# 1DDR3L_16bits.net
KiCad netlist of a schematic drawn in Altium Designer
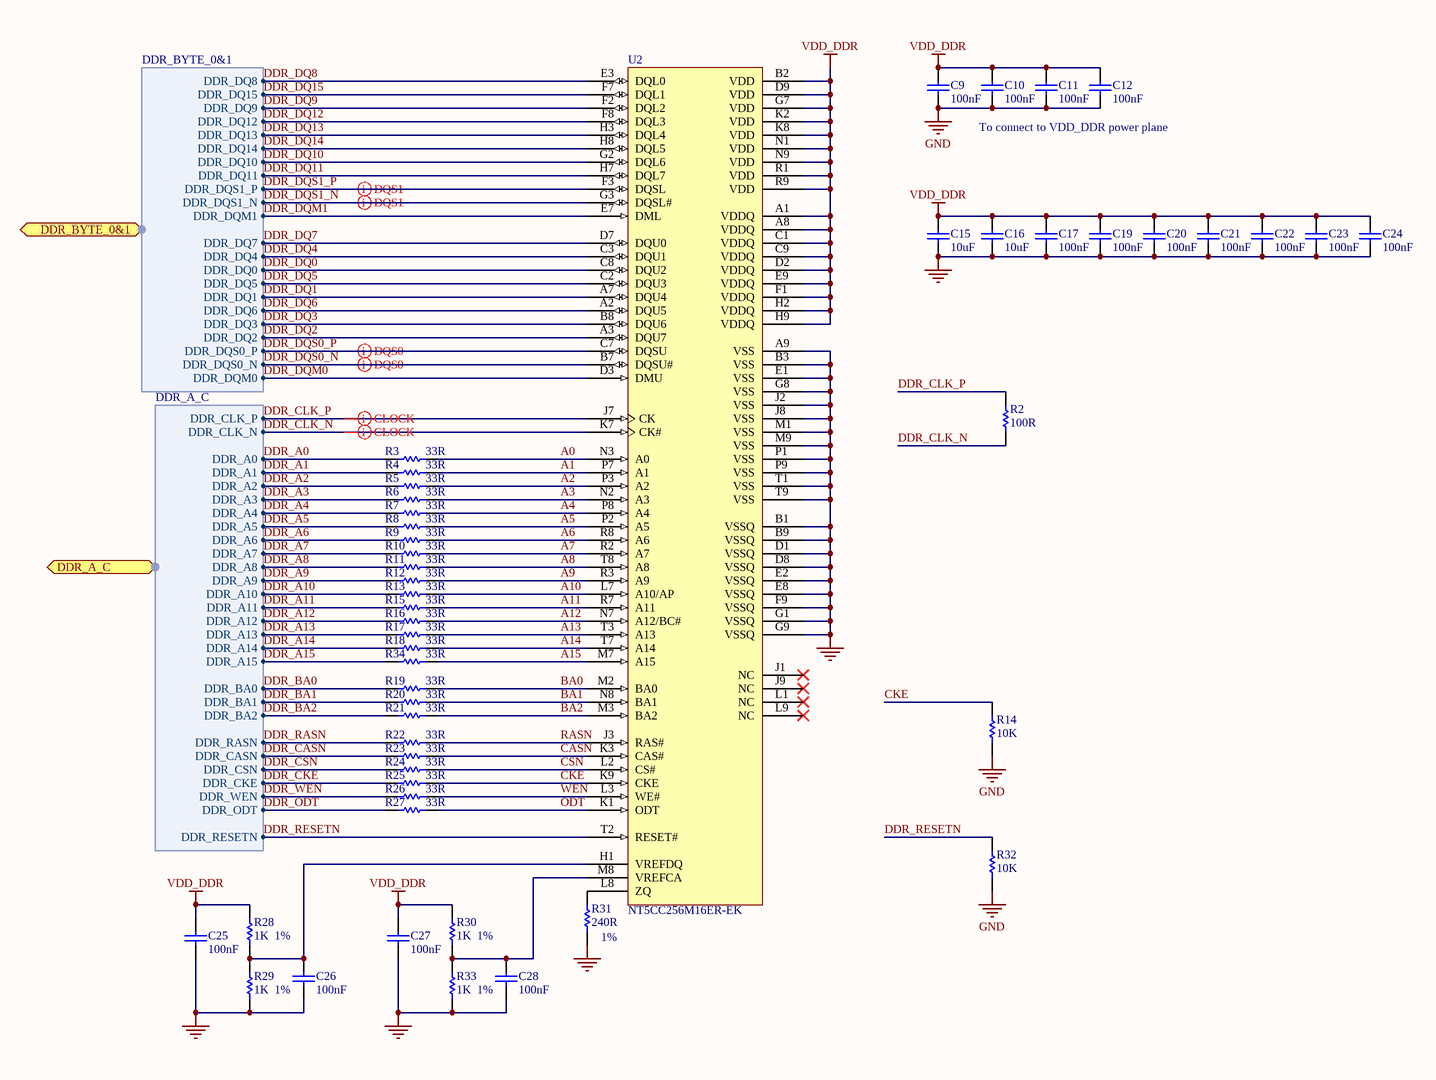
[diagram p0: 1DDR3L_16bits.SchDoc]

(export (version "E")
  (design (tool "Eeschema 10.0.6"))
  (components
    (comp (ref "C9")
      (value "100nF")
      (footprint "C0402")
      (description "Capacitor, MLCC, 100nF, 16V, X7R, 10%, 0402, T=0.5mm")
      (fields
        (field (name "INTERNAL_PART_NUMBER") "MCD-00006")
        (field (name "MANUFACTURER_PART_NUMBER") "CC0402KRX7R7BB104")
        (field (name "PROVIDED_BY") "SUBCO")
      )
      (libsource (lib "MCD_PARTS_database") (part "Capacitor"))
    )
    (comp (ref "C10")
      (value "100nF")
      (footprint "C0402")
      (description "Capacitor, MLCC, 100nF, 16V, X7R, 10%, 0402, T=0.5mm")
      (fields
        (field (name "INTERNAL_PART_NUMBER") "MCD-00006")
        (field (name "MANUFACTURER_PART_NUMBER") "CC0402KRX7R7BB104")
        (field (name "PROVIDED_BY") "SUBCO")
      )
      (libsource (lib "MCD_PARTS_database") (part "Capacitor"))
    )
    (comp (ref "C11")
      (value "100nF")
      (footprint "C0402")
      (description "Capacitor, MLCC, 100nF, 16V, X7R, 10%, 0402, T=0.5mm")
      (fields
        (field (name "INTERNAL_PART_NUMBER") "MCD-00006")
        (field (name "MANUFACTURER_PART_NUMBER") "CC0402KRX7R7BB104")
        (field (name "PROVIDED_BY") "SUBCO")
      )
      (libsource (lib "MCD_PARTS_database") (part "Capacitor"))
    )
    (comp (ref "C12")
      (value "100nF")
      (footprint "C0402")
      (description "Capacitor, MLCC, 100nF, 16V, X7R, 10%, 0402, T=0.5mm")
      (fields
        (field (name "INTERNAL_PART_NUMBER") "MCD-00006")
        (field (name "MANUFACTURER_PART_NUMBER") "CC0402KRX7R7BB104")
        (field (name "PROVIDED_BY") "SUBCO")
      )
      (libsource (lib "MCD_PARTS_database") (part "Capacitor"))
    )
    (comp (ref "C15")
      (value "10uF")
      (footprint "C0603")
      (description "Capacitor, MLCC, 10uF, 10V, X5R, 10%, 0603, T=0,8mm")
      (fields
        (field (name "INTERNAL_PART_NUMBER") "MCD-00099")
        (field (name "MANUFACTURER_PART_NUMBER") "GRM188R61A106KE69D")
        (field (name "PROVIDED_BY") "SUBCO")
      )
      (libsource (lib "MCD_PARTS_database") (part "Capacitor"))
    )
    (comp (ref "C16")
      (value "10uF")
      (footprint "C0603")
      (description "Capacitor, MLCC, 10uF, 10V, X5R, 10%, 0603, T=0,8mm")
      (fields
        (field (name "INTERNAL_PART_NUMBER") "MCD-00099")
        (field (name "MANUFACTURER_PART_NUMBER") "GRM188R61A106KE69D")
        (field (name "PROVIDED_BY") "SUBCO")
      )
      (libsource (lib "MCD_PARTS_database") (part "Capacitor"))
    )
    (comp (ref "C17")
      (value "100nF")
      (footprint "C0402")
      (description "Capacitor, MLCC, 100nF, 16V, X7R, 10%, 0402, T=0.5mm")
      (fields
        (field (name "INTERNAL_PART_NUMBER") "MCD-00006")
        (field (name "MANUFACTURER_PART_NUMBER") "CC0402KRX7R7BB104")
        (field (name "PROVIDED_BY") "SUBCO")
      )
      (libsource (lib "MCD_PARTS_database") (part "Capacitor"))
    )
    (comp (ref "C19")
      (value "100nF")
      (footprint "C0402")
      (description "Capacitor, MLCC, 100nF, 16V, X7R, 10%, 0402, T=0.5mm")
      (fields
        (field (name "INTERNAL_PART_NUMBER") "MCD-00006")
        (field (name "MANUFACTURER_PART_NUMBER") "CC0402KRX7R7BB104")
        (field (name "PROVIDED_BY") "SUBCO")
      )
      (libsource (lib "MCD_PARTS_database") (part "Capacitor"))
    )
    (comp (ref "C20")
      (value "100nF")
      (footprint "C0402")
      (description "Capacitor, MLCC, 100nF, 16V, X7R, 10%, 0402, T=0.5mm")
      (fields
        (field (name "INTERNAL_PART_NUMBER") "MCD-00006")
        (field (name "MANUFACTURER_PART_NUMBER") "CC0402KRX7R7BB104")
        (field (name "PROVIDED_BY") "SUBCO")
      )
      (libsource (lib "MCD_PARTS_database") (part "Capacitor"))
    )
    (comp (ref "C21")
      (value "100nF")
      (footprint "C0402")
      (description "Capacitor, MLCC, 100nF, 16V, X7R, 10%, 0402, T=0.5mm")
      (fields
        (field (name "INTERNAL_PART_NUMBER") "MCD-00006")
        (field (name "MANUFACTURER_PART_NUMBER") "CC0402KRX7R7BB104")
        (field (name "PROVIDED_BY") "SUBCO")
      )
      (libsource (lib "MCD_PARTS_database") (part "Capacitor"))
    )
    (comp (ref "C22")
      (value "100nF")
      (footprint "C0402")
      (description "Capacitor, MLCC, 100nF, 16V, X7R, 10%, 0402, T=0.5mm")
      (fields
        (field (name "INTERNAL_PART_NUMBER") "MCD-00006")
        (field (name "MANUFACTURER_PART_NUMBER") "CC0402KRX7R7BB104")
        (field (name "PROVIDED_BY") "SUBCO")
      )
      (libsource (lib "MCD_PARTS_database") (part "Capacitor"))
    )
    (comp (ref "C23")
      (value "100nF")
      (footprint "C0402")
      (description "Capacitor, MLCC, 100nF, 16V, X7R, 10%, 0402, T=0.5mm")
      (fields
        (field (name "INTERNAL_PART_NUMBER") "MCD-00006")
        (field (name "MANUFACTURER_PART_NUMBER") "CC0402KRX7R7BB104")
        (field (name "PROVIDED_BY") "SUBCO")
      )
      (libsource (lib "MCD_PARTS_database") (part "Capacitor"))
    )
    (comp (ref "C24")
      (value "100nF")
      (footprint "C0402")
      (description "Capacitor, MLCC, 100nF, 16V, X7R, 10%, 0402, T=0.5mm")
      (fields
        (field (name "INTERNAL_PART_NUMBER") "MCD-00006")
        (field (name "MANUFACTURER_PART_NUMBER") "CC0402KRX7R7BB104")
        (field (name "PROVIDED_BY") "SUBCO")
      )
      (libsource (lib "MCD_PARTS_database") (part "Capacitor"))
    )
    (comp (ref "C25")
      (value "100nF")
      (footprint "C0402")
      (description "Capacitor, MLCC, 100nF, 16V, X7R, 10%, 0402, T=0.5mm")
      (fields
        (field (name "INTERNAL_PART_NUMBER") "MCD-00006")
        (field (name "MANUFACTURER_PART_NUMBER") "CC0402KRX7R7BB104")
        (field (name "PROVIDED_BY") "SUBCO")
      )
      (libsource (lib "MCD_PARTS_database") (part "Capacitor"))
    )
    (comp (ref "C26")
      (value "100nF")
      (footprint "C0402")
      (description "Capacitor, MLCC, 100nF, 16V, X7R, 10%, 0402, T=0.5mm")
      (fields
        (field (name "INTERNAL_PART_NUMBER") "MCD-00006")
        (field (name "MANUFACTURER_PART_NUMBER") "CC0402KRX7R7BB104")
        (field (name "PROVIDED_BY") "SUBCO")
      )
      (libsource (lib "MCD_PARTS_database") (part "Capacitor"))
    )
    (comp (ref "C27")
      (value "100nF")
      (footprint "C0402")
      (description "Capacitor, MLCC, 100nF, 16V, X7R, 10%, 0402, T=0.5mm")
      (fields
        (field (name "INTERNAL_PART_NUMBER") "MCD-00006")
        (field (name "MANUFACTURER_PART_NUMBER") "CC0402KRX7R7BB104")
        (field (name "PROVIDED_BY") "SUBCO")
      )
      (libsource (lib "MCD_PARTS_database") (part "Capacitor"))
    )
    (comp (ref "C28")
      (value "100nF")
      (footprint "C0402")
      (description "Capacitor, MLCC, 100nF, 16V, X7R, 10%, 0402, T=0.5mm")
      (fields
        (field (name "INTERNAL_PART_NUMBER") "MCD-00006")
        (field (name "MANUFACTURER_PART_NUMBER") "CC0402KRX7R7BB104")
        (field (name "PROVIDED_BY") "SUBCO")
      )
      (libsource (lib "MCD_PARTS_database") (part "Capacitor"))
    )
    (comp (ref "R2")
      (value "100R")
      (footprint "R0402")
      (description "Resistor,100R,0402,1%,1/16W")
      (fields
        (field (name "INTERNAL_PART_NUMBER") "MCD-00119")
        (field (name "MANUFACTURER_PART_NUMBER") "RC0402FR-07100RL")
        (field (name "PROVIDED_BY") "SUBCO")
      )
      (libsource (lib "MCD_PARTS_database") (part "Resistor"))
    )
    (comp (ref "R3")
      (value "33R")
      (footprint "R0402")
      (description "Resistor,33R,0402,1%,1/16W")
      (fields
        (field (name "INTERNAL_PART_NUMBER") "MCD-00455")
        (field (name "MANUFACTURER_PART_NUMBER") "RC0402FR-0733RL")
        (field (name "PROVIDED_BY") "SUBCO")
      )
      (libsource (lib "MCD_PARTS_database") (part "Resistor"))
    )
    (comp (ref "R4")
      (value "33R")
      (footprint "R0402")
      (description "Resistor,33R,0402,1%,1/16W")
      (fields
        (field (name "INTERNAL_PART_NUMBER") "MCD-00455")
        (field (name "MANUFACTURER_PART_NUMBER") "RC0402FR-0733RL")
        (field (name "PROVIDED_BY") "SUBCO")
      )
      (libsource (lib "MCD_PARTS_database") (part "Resistor"))
    )
    (comp (ref "R5")
      (value "33R")
      (footprint "R0402")
      (description "Resistor,33R,0402,1%,1/16W")
      (fields
        (field (name "INTERNAL_PART_NUMBER") "MCD-00455")
        (field (name "MANUFACTURER_PART_NUMBER") "RC0402FR-0733RL")
        (field (name "PROVIDED_BY") "SUBCO")
      )
      (libsource (lib "MCD_PARTS_database") (part "Resistor"))
    )
    (comp (ref "R6")
      (value "33R")
      (footprint "R0402")
      (description "Resistor,33R,0402,1%,1/16W")
      (fields
        (field (name "INTERNAL_PART_NUMBER") "MCD-00455")
        (field (name "MANUFACTURER_PART_NUMBER") "RC0402FR-0733RL")
        (field (name "PROVIDED_BY") "SUBCO")
      )
      (libsource (lib "MCD_PARTS_database") (part "Resistor"))
    )
    (comp (ref "R7")
      (value "33R")
      (footprint "R0402")
      (description "Resistor,33R,0402,1%,1/16W")
      (fields
        (field (name "INTERNAL_PART_NUMBER") "MCD-00455")
        (field (name "MANUFACTURER_PART_NUMBER") "RC0402FR-0733RL")
        (field (name "PROVIDED_BY") "SUBCO")
      )
      (libsource (lib "MCD_PARTS_database") (part "Resistor"))
    )
    (comp (ref "R8")
      (value "33R")
      (footprint "R0402")
      (description "Resistor,33R,0402,1%,1/16W")
      (fields
        (field (name "INTERNAL_PART_NUMBER") "MCD-00455")
        (field (name "MANUFACTURER_PART_NUMBER") "RC0402FR-0733RL")
        (field (name "PROVIDED_BY") "SUBCO")
      )
      (libsource (lib "MCD_PARTS_database") (part "Resistor"))
    )
    (comp (ref "R9")
      (value "33R")
      (footprint "R0402")
      (description "Resistor,33R,0402,1%,1/16W")
      (fields
        (field (name "INTERNAL_PART_NUMBER") "MCD-00455")
        (field (name "MANUFACTURER_PART_NUMBER") "RC0402FR-0733RL")
        (field (name "PROVIDED_BY") "SUBCO")
      )
      (libsource (lib "MCD_PARTS_database") (part "Resistor"))
    )
    (comp (ref "R10")
      (value "33R")
      (footprint "R0402")
      (description "Resistor,33R,0402,1%,1/16W")
      (fields
        (field (name "INTERNAL_PART_NUMBER") "MCD-00455")
        (field (name "MANUFACTURER_PART_NUMBER") "RC0402FR-0733RL")
        (field (name "PROVIDED_BY") "SUBCO")
      )
      (libsource (lib "MCD_PARTS_database") (part "Resistor"))
    )
    (comp (ref "R11")
      (value "33R")
      (footprint "R0402")
      (description "Resistor,33R,0402,1%,1/16W")
      (fields
        (field (name "INTERNAL_PART_NUMBER") "MCD-00455")
        (field (name "MANUFACTURER_PART_NUMBER") "RC0402FR-0733RL")
        (field (name "PROVIDED_BY") "SUBCO")
      )
      (libsource (lib "MCD_PARTS_database") (part "Resistor"))
    )
    (comp (ref "R12")
      (value "33R")
      (footprint "R0402")
      (description "Resistor,33R,0402,1%,1/16W")
      (fields
        (field (name "INTERNAL_PART_NUMBER") "MCD-00455")
        (field (name "MANUFACTURER_PART_NUMBER") "RC0402FR-0733RL")
        (field (name "PROVIDED_BY") "SUBCO")
      )
      (libsource (lib "MCD_PARTS_database") (part "Resistor"))
    )
    (comp (ref "R13")
      (value "33R")
      (footprint "R0402")
      (description "Resistor,33R,0402,1%,1/16W")
      (fields
        (field (name "INTERNAL_PART_NUMBER") "MCD-00455")
        (field (name "MANUFACTURER_PART_NUMBER") "RC0402FR-0733RL")
        (field (name "PROVIDED_BY") "SUBCO")
      )
      (libsource (lib "MCD_PARTS_database") (part "Resistor"))
    )
    (comp (ref "R14")
      (value "10K")
      (footprint "R0402")
      (description "Resistor,10K,0402,1%,1/16W")
      (fields
        (field (name "INTERNAL_PART_NUMBER") "MCD-00053")
        (field (name "MANUFACTURER_PART_NUMBER") "RC0402FR-0710KL")
        (field (name "PROVIDED_BY") "SUBCO")
      )
      (libsource (lib "MCD_PARTS_database") (part "Resistor"))
    )
    (comp (ref "R15")
      (value "33R")
      (footprint "R0402")
      (description "Resistor,33R,0402,1%,1/16W")
      (fields
        (field (name "INTERNAL_PART_NUMBER") "MCD-00455")
        (field (name "MANUFACTURER_PART_NUMBER") "RC0402FR-0733RL")
        (field (name "PROVIDED_BY") "SUBCO")
      )
      (libsource (lib "MCD_PARTS_database") (part "Resistor"))
    )
    (comp (ref "R16")
      (value "33R")
      (footprint "R0402")
      (description "Resistor,33R,0402,1%,1/16W")
      (fields
        (field (name "INTERNAL_PART_NUMBER") "MCD-00455")
        (field (name "MANUFACTURER_PART_NUMBER") "RC0402FR-0733RL")
        (field (name "PROVIDED_BY") "SUBCO")
      )
      (libsource (lib "MCD_PARTS_database") (part "Resistor"))
    )
    (comp (ref "R17")
      (value "33R")
      (footprint "R0402")
      (description "Resistor,33R,0402,1%,1/16W")
      (fields
        (field (name "INTERNAL_PART_NUMBER") "MCD-00455")
        (field (name "MANUFACTURER_PART_NUMBER") "RC0402FR-0733RL")
        (field (name "PROVIDED_BY") "SUBCO")
      )
      (libsource (lib "MCD_PARTS_database") (part "Resistor"))
    )
    (comp (ref "R18")
      (value "33R")
      (footprint "R0402")
      (description "Resistor,33R,0402,1%,1/16W")
      (fields
        (field (name "INTERNAL_PART_NUMBER") "MCD-00455")
        (field (name "MANUFACTURER_PART_NUMBER") "RC0402FR-0733RL")
        (field (name "PROVIDED_BY") "SUBCO")
      )
      (libsource (lib "MCD_PARTS_database") (part "Resistor"))
    )
    (comp (ref "R19")
      (value "33R")
      (footprint "R0402")
      (description "Resistor,33R,0402,1%,1/16W")
      (fields
        (field (name "INTERNAL_PART_NUMBER") "MCD-00455")
        (field (name "MANUFACTURER_PART_NUMBER") "RC0402FR-0733RL")
        (field (name "PROVIDED_BY") "SUBCO")
      )
      (libsource (lib "MCD_PARTS_database") (part "Resistor"))
    )
    (comp (ref "R20")
      (value "33R")
      (footprint "R0402")
      (description "Resistor,33R,0402,1%,1/16W")
      (fields
        (field (name "INTERNAL_PART_NUMBER") "MCD-00455")
        (field (name "MANUFACTURER_PART_NUMBER") "RC0402FR-0733RL")
        (field (name "PROVIDED_BY") "SUBCO")
      )
      (libsource (lib "MCD_PARTS_database") (part "Resistor"))
    )
    (comp (ref "R21")
      (value "33R")
      (footprint "R0402")
      (description "Resistor,33R,0402,1%,1/16W")
      (fields
        (field (name "INTERNAL_PART_NUMBER") "MCD-00455")
        (field (name "MANUFACTURER_PART_NUMBER") "RC0402FR-0733RL")
        (field (name "PROVIDED_BY") "SUBCO")
      )
      (libsource (lib "MCD_PARTS_database") (part "Resistor"))
    )
    (comp (ref "R22")
      (value "33R")
      (footprint "R0402")
      (description "Resistor,33R,0402,1%,1/16W")
      (fields
        (field (name "INTERNAL_PART_NUMBER") "MCD-00455")
        (field (name "MANUFACTURER_PART_NUMBER") "RC0402FR-0733RL")
        (field (name "PROVIDED_BY") "SUBCO")
      )
      (libsource (lib "MCD_PARTS_database") (part "Resistor"))
    )
    (comp (ref "R23")
      (value "33R")
      (footprint "R0402")
      (description "Resistor,33R,0402,1%,1/16W")
      (fields
        (field (name "INTERNAL_PART_NUMBER") "MCD-00455")
        (field (name "MANUFACTURER_PART_NUMBER") "RC0402FR-0733RL")
        (field (name "PROVIDED_BY") "SUBCO")
      )
      (libsource (lib "MCD_PARTS_database") (part "Resistor"))
    )
    (comp (ref "R24")
      (value "33R")
      (footprint "R0402")
      (description "Resistor,33R,0402,1%,1/16W")
      (fields
        (field (name "INTERNAL_PART_NUMBER") "MCD-00455")
        (field (name "MANUFACTURER_PART_NUMBER") "RC0402FR-0733RL")
        (field (name "PROVIDED_BY") "SUBCO")
      )
      (libsource (lib "MCD_PARTS_database") (part "Resistor"))
    )
    (comp (ref "R25")
      (value "33R")
      (footprint "R0402")
      (description "Resistor,33R,0402,1%,1/16W")
      (fields
        (field (name "INTERNAL_PART_NUMBER") "MCD-00455")
        (field (name "MANUFACTURER_PART_NUMBER") "RC0402FR-0733RL")
        (field (name "PROVIDED_BY") "SUBCO")
      )
      (libsource (lib "MCD_PARTS_database") (part "Resistor"))
    )
    (comp (ref "R26")
      (value "33R")
      (footprint "R0402")
      (description "Resistor,33R,0402,1%,1/16W")
      (fields
        (field (name "INTERNAL_PART_NUMBER") "MCD-00455")
        (field (name "MANUFACTURER_PART_NUMBER") "RC0402FR-0733RL")
        (field (name "PROVIDED_BY") "SUBCO")
      )
      (libsource (lib "MCD_PARTS_database") (part "Resistor"))
    )
    (comp (ref "R27")
      (value "33R")
      (footprint "R0402")
      (description "Resistor,33R,0402,1%,1/16W")
      (fields
        (field (name "INTERNAL_PART_NUMBER") "MCD-00455")
        (field (name "MANUFACTURER_PART_NUMBER") "RC0402FR-0733RL")
        (field (name "PROVIDED_BY") "SUBCO")
      )
      (libsource (lib "MCD_PARTS_database") (part "Resistor"))
    )
    (comp (ref "R28")
      (value "1K")
      (footprint "R0402")
      (description "Resistor,1K,0402,1%,1/16W")
      (fields
        (field (name "INTERNAL_PART_NUMBER") "MCD-00061")
        (field (name "MANUFACTURER_PART_NUMBER") "RC0402FR-071KL")
        (field (name "PROVIDED_BY") "SUBCO")
      )
      (libsource (lib "MCD_PARTS_database") (part "Resistor"))
    )
    (comp (ref "R29")
      (value "1K")
      (footprint "R0402")
      (description "Resistor,1K,0402,1%,1/16W")
      (fields
        (field (name "INTERNAL_PART_NUMBER") "MCD-00061")
        (field (name "MANUFACTURER_PART_NUMBER") "RC0402FR-071KL")
        (field (name "PROVIDED_BY") "SUBCO")
      )
      (libsource (lib "MCD_PARTS_database") (part "Resistor"))
    )
    (comp (ref "R30")
      (value "1K")
      (footprint "R0402")
      (description "Resistor,1K,0402,1%,1/16W")
      (fields
        (field (name "INTERNAL_PART_NUMBER") "MCD-00061")
        (field (name "MANUFACTURER_PART_NUMBER") "RC0402FR-071KL")
        (field (name "PROVIDED_BY") "SUBCO")
      )
      (libsource (lib "MCD_PARTS_database") (part "Resistor"))
    )
    (comp (ref "R31")
      (value "240R")
      (footprint "R0402")
      (description "Resistor,240R,0402,1%,1/16W")
      (fields
        (field (name "INTERNAL_PART_NUMBER") "MCD-00120")
        (field (name "MANUFACTURER_PART_NUMBER") "RC0402FR-07240RL")
        (field (name "PROVIDED_BY") "SUBCO")
      )
      (libsource (lib "MCD_PARTS_database") (part "Resistor"))
    )
    (comp (ref "R32")
      (value "10K")
      (footprint "R0402")
      (description "Resistor,10K,0402,1%,1/16W")
      (fields
        (field (name "INTERNAL_PART_NUMBER") "MCD-00053")
        (field (name "MANUFACTURER_PART_NUMBER") "RC0402FR-0710KL")
        (field (name "PROVIDED_BY") "SUBCO")
      )
      (libsource (lib "MCD_PARTS_database") (part "Resistor"))
    )
    (comp (ref "R33")
      (value "1K")
      (footprint "R0402")
      (description "Resistor,1K,0402,1%,1/16W")
      (fields
        (field (name "INTERNAL_PART_NUMBER") "MCD-00061")
        (field (name "MANUFACTURER_PART_NUMBER") "RC0402FR-071KL")
        (field (name "PROVIDED_BY") "SUBCO")
      )
      (libsource (lib "MCD_PARTS_database") (part "Resistor"))
    )
    (comp (ref "R34")
      (value "33R")
      (footprint "R0402")
      (description "Resistor,33R,0402,1%,1/16W")
      (fields
        (field (name "INTERNAL_PART_NUMBER") "MCD-00455")
        (field (name "MANUFACTURER_PART_NUMBER") "RC0402FR-0733RL")
        (field (name "PROVIDED_BY") "SUBCO")
      )
      (libsource (lib "MCD_PARTS_database") (part "Resistor"))
    )
    (comp (ref "U2")
      (value "NT5CC256M16ER-EK")
      (footprint "ICC_VFBGA96_9x13_P080")
      (description "Memory,DDR3L,4Gb,256Mbx16,933Mhz,1V35,TFBGA")
      (fields
        (field (name "INTERNAL_PART_NUMBER") "MCD-01811")
        (field (name "MANUFACTURER") "NANYA")
        (field (name "PROVIDED_BY") "SUBCO")
      )
      (libsource (lib "MCD_PARTS_database") (part "NT5CC256M16ER-EK"))
    )
  )
  (nets
    (net (code "3") (name "/A0") (class "Default")
      (node (ref "R3") (pin "2") (pinfunction "2_2") (pintype "passive"))
      (node (ref "U2") (pin "N3") (pinfunction "A0_N3") (pintype "input"))
    )
    (net (code "4") (name "/A1") (class "Default")
      (node (ref "R4") (pin "2") (pinfunction "2_2") (pintype "passive"))
      (node (ref "U2") (pin "P7") (pinfunction "A1_P7") (pintype "input"))
    )
    (net (code "5") (name "/A2") (class "Default")
      (node (ref "R5") (pin "2") (pinfunction "2_2") (pintype "passive"))
      (node (ref "U2") (pin "P3") (pinfunction "A2_P3") (pintype "input"))
    )
    (net (code "6") (name "/A3") (class "Default")
      (node (ref "R6") (pin "2") (pinfunction "2_2") (pintype "passive"))
      (node (ref "U2") (pin "N2") (pinfunction "A3_N2") (pintype "input"))
    )
    (net (code "7") (name "/A4") (class "Default")
      (node (ref "R7") (pin "2") (pinfunction "2_2") (pintype "passive"))
      (node (ref "U2") (pin "P8") (pinfunction "A4_P8") (pintype "input"))
    )
    (net (code "8") (name "/A5") (class "Default")
      (node (ref "R8") (pin "2") (pinfunction "2_2") (pintype "passive"))
      (node (ref "U2") (pin "P2") (pinfunction "A5_P2") (pintype "input"))
    )
    (net (code "9") (name "/A6") (class "Default")
      (node (ref "R9") (pin "2") (pinfunction "2_2") (pintype "passive"))
      (node (ref "U2") (pin "R8") (pinfunction "A6_R8") (pintype "input"))
    )
    (net (code "10") (name "/A7") (class "Default")
      (node (ref "R10") (pin "2") (pinfunction "2_2") (pintype "passive"))
      (node (ref "U2") (pin "R2") (pinfunction "A7_R2") (pintype "input"))
    )
    (net (code "11") (name "/A8") (class "Default")
      (node (ref "R11") (pin "2") (pinfunction "2_2") (pintype "passive"))
      (node (ref "U2") (pin "T8") (pinfunction "A8_T8") (pintype "input"))
    )
    (net (code "12") (name "/A9") (class "Default")
      (node (ref "R12") (pin "2") (pinfunction "2_2") (pintype "passive"))
      (node (ref "U2") (pin "R3") (pinfunction "A9_R3") (pintype "input"))
    )
    (net (code "13") (name "/A10") (class "Default")
      (node (ref "R13") (pin "2") (pinfunction "2_2") (pintype "passive"))
      (node (ref "U2") (pin "L7") (pinfunction "A10/AP_L7") (pintype "input"))
    )
    (net (code "14") (name "/A11") (class "Default")
      (node (ref "R15") (pin "2") (pinfunction "2_2") (pintype "passive"))
      (node (ref "U2") (pin "R7") (pinfunction "A11_R7") (pintype "input"))
    )
    (net (code "15") (name "/A12") (class "Default")
      (node (ref "R16") (pin "2") (pinfunction "2_2") (pintype "passive"))
      (node (ref "U2") (pin "N7") (pinfunction "A12/BC#_N7") (pintype "input"))
    )
    (net (code "16") (name "/A13") (class "Default")
      (node (ref "R17") (pin "2") (pinfunction "2_2") (pintype "passive"))
      (node (ref "U2") (pin "T3") (pinfunction "A13_T3") (pintype "input"))
    )
    (net (code "17") (name "/A14") (class "Default")
      (node (ref "R18") (pin "2") (pinfunction "2_2") (pintype "passive"))
      (node (ref "U2") (pin "T7") (pinfunction "A14_T7") (pintype "input"))
    )
    (net (code "18") (name "/A15") (class "Default")
      (node (ref "R34") (pin "2") (pinfunction "2_2") (pintype "passive"))
      (node (ref "U2") (pin "M7") (pinfunction "A15_M7") (pintype "input"))
    )
    (net (code "19") (name "/BA0") (class "Default")
      (node (ref "R19") (pin "2") (pinfunction "2_2") (pintype "passive"))
      (node (ref "U2") (pin "M2") (pinfunction "BA0_M2") (pintype "input"))
    )
    (net (code "20") (name "/BA1") (class "Default")
      (node (ref "R20") (pin "2") (pinfunction "2_2") (pintype "passive"))
      (node (ref "U2") (pin "N8") (pinfunction "BA1_N8") (pintype "input"))
    )
    (net (code "21") (name "/BA2") (class "Default")
      (node (ref "R21") (pin "2") (pinfunction "2_2") (pintype "passive"))
      (node (ref "U2") (pin "M3") (pinfunction "BA2_M3") (pintype "input"))
    )
    (net (code "22") (name "/CASN") (class "Default")
      (node (ref "R23") (pin "2") (pinfunction "2_2") (pintype "passive"))
      (node (ref "U2") (pin "K3") (pinfunction "CAS#_K3") (pintype "input"))
    )
    (net (code "23") (name "/CKE") (class "Default")
      (node (ref "R14") (pin "2") (pinfunction "2_2") (pintype "passive"))
      (node (ref "R25") (pin "2") (pinfunction "2_2") (pintype "passive"))
      (node (ref "U2") (pin "K9") (pinfunction "CKE_K9") (pintype "input"))
    )
    (net (code "24") (name "/CSN") (class "Default")
      (node (ref "R24") (pin "2") (pinfunction "2_2") (pintype "passive"))
      (node (ref "U2") (pin "L2") (pinfunction "CS#_L2") (pintype "input"))
    )
    (net (code "25") (name "/DDR_A0") (class "Default")
      (node (ref "R3") (pin "1") (pinfunction "1_1") (pintype "passive"))
    )
    (net (code "26") (name "/DDR_A1") (class "Default")
      (node (ref "R4") (pin "1") (pinfunction "1_1") (pintype "passive"))
    )
    (net (code "27") (name "/DDR_A2") (class "Default")
      (node (ref "R5") (pin "1") (pinfunction "1_1") (pintype "passive"))
    )
    (net (code "28") (name "/DDR_A3") (class "Default")
      (node (ref "R6") (pin "1") (pinfunction "1_1") (pintype "passive"))
    )
    (net (code "29") (name "/DDR_A4") (class "Default")
      (node (ref "R7") (pin "1") (pinfunction "1_1") (pintype "passive"))
    )
    (net (code "30") (name "/DDR_A5") (class "Default")
      (node (ref "R8") (pin "1") (pinfunction "1_1") (pintype "passive"))
    )
    (net (code "31") (name "/DDR_A6") (class "Default")
      (node (ref "R9") (pin "1") (pinfunction "1_1") (pintype "passive"))
    )
    (net (code "32") (name "/DDR_A7") (class "Default")
      (node (ref "R10") (pin "1") (pinfunction "1_1") (pintype "passive"))
    )
    (net (code "33") (name "/DDR_A8") (class "Default")
      (node (ref "R11") (pin "1") (pinfunction "1_1") (pintype "passive"))
    )
    (net (code "34") (name "/DDR_A9") (class "Default")
      (node (ref "R12") (pin "1") (pinfunction "1_1") (pintype "passive"))
    )
    (net (code "35") (name "/DDR_A10") (class "Default")
      (node (ref "R13") (pin "1") (pinfunction "1_1") (pintype "passive"))
    )
    (net (code "36") (name "/DDR_A11") (class "Default")
      (node (ref "R15") (pin "1") (pinfunction "1_1") (pintype "passive"))
    )
    (net (code "37") (name "/DDR_A12") (class "Default")
      (node (ref "R16") (pin "1") (pinfunction "1_1") (pintype "passive"))
    )
    (net (code "38") (name "/DDR_A13") (class "Default")
      (node (ref "R17") (pin "1") (pinfunction "1_1") (pintype "passive"))
    )
    (net (code "39") (name "/DDR_A14") (class "Default")
      (node (ref "R18") (pin "1") (pinfunction "1_1") (pintype "passive"))
    )
    (net (code "40") (name "/DDR_A15") (class "Default")
      (node (ref "R34") (pin "1") (pinfunction "1_1") (pintype "passive"))
    )
    (net (code "41") (name "/DDR_BA0") (class "Default")
      (node (ref "R19") (pin "1") (pinfunction "1_1") (pintype "passive"))
    )
    (net (code "42") (name "/DDR_BA1") (class "Default")
      (node (ref "R20") (pin "1") (pinfunction "1_1") (pintype "passive"))
    )
    (net (code "43") (name "/DDR_BA2") (class "Default")
      (node (ref "R21") (pin "1") (pinfunction "1_1") (pintype "passive"))
    )
    (net (code "44") (name "/DDR_CASN") (class "Default")
      (node (ref "R23") (pin "1") (pinfunction "1_1") (pintype "passive"))
    )
    (net (code "45") (name "/DDR_CKE") (class "Default")
      (node (ref "R25") (pin "1") (pinfunction "1_1") (pintype "passive"))
    )
    (net (code "46") (name "/DDR_CLK_N") (class "Default")
      (node (ref "R2") (pin "1") (pinfunction "1_1") (pintype "passive"))
      (node (ref "U2") (pin "K7") (pinfunction "CK#_K7") (pintype "input"))
    )
    (net (code "47") (name "/DDR_CLK_P") (class "Default")
      (node (ref "R2") (pin "2") (pinfunction "2_2") (pintype "passive"))
      (node (ref "U2") (pin "J7") (pinfunction "CK_J7") (pintype "input"))
    )
    (net (code "48") (name "/DDR_CSN") (class "Default")
      (node (ref "R24") (pin "1") (pinfunction "1_1") (pintype "passive"))
    )
    (net (code "49") (name "/DDR_DQ0") (class "Default")
      (node (ref "U2") (pin "C8") (pinfunction "DQU2_C8") (pintype "bidirectional"))
    )
    (net (code "50") (name "/DDR_DQ1") (class "Default")
      (node (ref "U2") (pin "A7") (pinfunction "DQU4_A7") (pintype "bidirectional"))
    )
    (net (code "51") (name "/DDR_DQ2") (class "Default")
      (node (ref "U2") (pin "A3") (pinfunction "DQU7_A3") (pintype "bidirectional"))
    )
    (net (code "52") (name "/DDR_DQ3") (class "Default")
      (node (ref "U2") (pin "B8") (pinfunction "DQU6_B8") (pintype "bidirectional"))
    )
    (net (code "53") (name "/DDR_DQ4") (class "Default")
      (node (ref "U2") (pin "C3") (pinfunction "DQU1_C3") (pintype "bidirectional"))
    )
    (net (code "54") (name "/DDR_DQ5") (class "Default")
      (node (ref "U2") (pin "C2") (pinfunction "DQU3_C2") (pintype "bidirectional"))
    )
    (net (code "55") (name "/DDR_DQ6") (class "Default")
      (node (ref "U2") (pin "A2") (pinfunction "DQU5_A2") (pintype "bidirectional"))
    )
    (net (code "56") (name "/DDR_DQ7") (class "Default")
      (node (ref "U2") (pin "D7") (pinfunction "DQU0_D7") (pintype "bidirectional"))
    )
    (net (code "57") (name "/DDR_DQ8") (class "Default")
      (node (ref "U2") (pin "E3") (pinfunction "DQL0_E3") (pintype "bidirectional"))
    )
    (net (code "58") (name "/DDR_DQ9") (class "Default")
      (node (ref "U2") (pin "F2") (pinfunction "DQL2_F2") (pintype "bidirectional"))
    )
    (net (code "59") (name "/DDR_DQ10") (class "Default")
      (node (ref "U2") (pin "G2") (pinfunction "DQL6_G2") (pintype "bidirectional"))
    )
    (net (code "60") (name "/DDR_DQ11") (class "Default")
      (node (ref "U2") (pin "H7") (pinfunction "DQL7_H7") (pintype "bidirectional"))
    )
    (net (code "61") (name "/DDR_DQ12") (class "Default")
      (node (ref "U2") (pin "F8") (pinfunction "DQL3_F8") (pintype "bidirectional"))
    )
    (net (code "62") (name "/DDR_DQ13") (class "Default")
      (node (ref "U2") (pin "H3") (pinfunction "DQL4_H3") (pintype "bidirectional"))
    )
    (net (code "63") (name "/DDR_DQ14") (class "Default")
      (node (ref "U2") (pin "H8") (pinfunction "DQL5_H8") (pintype "bidirectional"))
    )
    (net (code "64") (name "/DDR_DQ15") (class "Default")
      (node (ref "U2") (pin "F7") (pinfunction "DQL1_F7") (pintype "bidirectional"))
    )
    (net (code "65") (name "/DDR_DQM0") (class "Default")
      (node (ref "U2") (pin "D3") (pinfunction "DMU_D3") (pintype "input"))
    )
    (net (code "66") (name "/DDR_DQM1") (class "Default")
      (node (ref "U2") (pin "E7") (pinfunction "DML_E7") (pintype "input"))
    )
    (net (code "67") (name "/DDR_DQS0_N") (class "Default")
      (node (ref "U2") (pin "B7") (pinfunction "DQSU#_B7") (pintype "bidirectional"))
    )
    (net (code "68") (name "/DDR_DQS0_P") (class "Default")
      (node (ref "U2") (pin "C7") (pinfunction "DQSU_C7") (pintype "bidirectional"))
    )
    (net (code "69") (name "/DDR_DQS1_N") (class "Default")
      (node (ref "U2") (pin "G3") (pinfunction "DQSL#_G3") (pintype "bidirectional"))
    )
    (net (code "70") (name "/DDR_DQS1_P") (class "Default")
      (node (ref "U2") (pin "F3") (pinfunction "DQSL_F3") (pintype "bidirectional"))
    )
    (net (code "71") (name "/DDR_ODT") (class "Default")
      (node (ref "R27") (pin "1") (pinfunction "1_1") (pintype "passive"))
    )
    (net (code "72") (name "/DDR_RASN") (class "Default")
      (node (ref "R22") (pin "1") (pinfunction "1_1") (pintype "passive"))
    )
    (net (code "73") (name "/DDR_RESETN") (class "Default")
      (node (ref "R32") (pin "2") (pinfunction "2_2") (pintype "passive"))
      (node (ref "U2") (pin "T2") (pinfunction "RESET#_T2") (pintype "input"))
    )
    (net (code "74") (name "/DDR_WEN") (class "Default")
      (node (ref "R26") (pin "1") (pinfunction "1_1") (pintype "passive"))
    )
    (net (code "75") (name "/ODT") (class "Default")
      (node (ref "R27") (pin "2") (pinfunction "2_2") (pintype "passive"))
      (node (ref "U2") (pin "K1") (pinfunction "ODT_K1") (pintype "input"))
    )
    (net (code "76") (name "/RASN") (class "Default")
      (node (ref "R22") (pin "2") (pinfunction "2_2") (pintype "passive"))
      (node (ref "U2") (pin "J3") (pinfunction "RAS#_J3") (pintype "input"))
    )
    (net (code "77") (name "/WEN") (class "Default")
      (node (ref "R26") (pin "2") (pinfunction "2_2") (pintype "passive"))
      (node (ref "U2") (pin "L3") (pinfunction "WE#_L3") (pintype "input"))
    )
    (net (code "80") (name "GND") (class "Default")
      (node (ref "C10") (pin "1") (pinfunction "1_1") (pintype "passive"))
      (node (ref "C11") (pin "1") (pinfunction "1_1") (pintype "passive"))
      (node (ref "C12") (pin "1") (pinfunction "1_1") (pintype "passive"))
      (node (ref "C15") (pin "1") (pinfunction "1_1") (pintype "passive"))
      (node (ref "C16") (pin "1") (pinfunction "1_1") (pintype "passive"))
      (node (ref "C17") (pin "1") (pinfunction "1_1") (pintype "passive"))
      (node (ref "C19") (pin "1") (pinfunction "1_1") (pintype "passive"))
      (node (ref "C20") (pin "1") (pinfunction "1_1") (pintype "passive"))
      (node (ref "C21") (pin "1") (pinfunction "1_1") (pintype "passive"))
      (node (ref "C22") (pin "2") (pinfunction "2_2") (pintype "passive"))
      (node (ref "C23") (pin "1") (pinfunction "1_1") (pintype "passive"))
      (node (ref "C24") (pin "1") (pinfunction "1_1") (pintype "passive"))
      (node (ref "C25") (pin "1") (pinfunction "1_1") (pintype "passive"))
      (node (ref "C26") (pin "1") (pinfunction "1_1") (pintype "passive"))
      (node (ref "C27") (pin "1") (pinfunction "1_1") (pintype "passive"))
      (node (ref "C28") (pin "1") (pinfunction "1_1") (pintype "passive"))
      (node (ref "C9") (pin "1") (pinfunction "1_1") (pintype "passive"))
      (node (ref "R14") (pin "1") (pinfunction "1_1") (pintype "passive"))
      (node (ref "R29") (pin "1") (pinfunction "1_1") (pintype "passive"))
      (node (ref "R31") (pin "1") (pinfunction "1_1") (pintype "passive"))
      (node (ref "R32") (pin "1") (pinfunction "1_1") (pintype "passive"))
      (node (ref "R33") (pin "1") (pinfunction "1_1") (pintype "passive"))
      (node (ref "U2") (pin "A9") (pinfunction "VSS_A9") (pintype "power_in"))
      (node (ref "U2") (pin "B1") (pinfunction "VSSQ_B1") (pintype "power_in"))
      (node (ref "U2") (pin "B3") (pinfunction "VSS_B3") (pintype "power_in"))
      (node (ref "U2") (pin "B9") (pinfunction "VSSQ_B9") (pintype "power_in"))
      (node (ref "U2") (pin "D1") (pinfunction "VSSQ_D1") (pintype "power_in"))
      (node (ref "U2") (pin "D8") (pinfunction "VSSQ_D8") (pintype "power_in"))
      (node (ref "U2") (pin "E1") (pinfunction "VSS_E1") (pintype "power_in"))
      (node (ref "U2") (pin "E2") (pinfunction "VSSQ_E2") (pintype "power_in"))
      (node (ref "U2") (pin "E8") (pinfunction "VSSQ_E8") (pintype "power_in"))
      (node (ref "U2") (pin "F9") (pinfunction "VSSQ_F9") (pintype "power_in"))
      (node (ref "U2") (pin "G1") (pinfunction "VSSQ_G1") (pintype "power_in"))
      (node (ref "U2") (pin "G8") (pinfunction "VSS_G8") (pintype "power_in"))
      (node (ref "U2") (pin "G9") (pinfunction "VSSQ_G9") (pintype "power_in"))
      (node (ref "U2") (pin "J2") (pinfunction "VSS_J2") (pintype "power_in"))
      (node (ref "U2") (pin "J8") (pinfunction "VSS_J8") (pintype "power_in"))
      (node (ref "U2") (pin "M1") (pinfunction "VSS_M1") (pintype "power_in"))
      (node (ref "U2") (pin "M9") (pinfunction "VSS_M9") (pintype "power_in"))
      (node (ref "U2") (pin "P1") (pinfunction "VSS_P1") (pintype "power_in"))
      (node (ref "U2") (pin "P9") (pinfunction "VSS_P9") (pintype "power_in"))
      (node (ref "U2") (pin "T1") (pinfunction "VSS_T1") (pintype "power_in"))
      (node (ref "U2") (pin "T9") (pinfunction "VSS_T9") (pintype "power_in"))
    )
    (net (code "81") (name "Net-(U2-VREFCA)") (class "Default")
      (node (ref "C28") (pin "2") (pinfunction "2_2") (pintype "passive"))
      (node (ref "R30") (pin "1") (pinfunction "1_1") (pintype "passive"))
      (node (ref "R33") (pin "2") (pinfunction "2_2") (pintype "passive"))
      (node (ref "U2") (pin "M8") (pinfunction "VREFCA_M8") (pintype "passive"))
    )
    (net (code "82") (name "Net-(U2-VREFDQ)") (class "Default")
      (node (ref "C26") (pin "2") (pinfunction "2_2") (pintype "passive"))
      (node (ref "R28") (pin "1") (pinfunction "1_1") (pintype "passive"))
      (node (ref "R29") (pin "2") (pinfunction "2_2") (pintype "passive"))
      (node (ref "U2") (pin "H1") (pinfunction "VREFDQ_H1") (pintype "passive"))
    )
    (net (code "83") (name "Net-(U2-ZQ)") (class "Default")
      (node (ref "R31") (pin "2") (pinfunction "2_2") (pintype "passive"))
      (node (ref "U2") (pin "L8") (pinfunction "ZQ_L8") (pintype "passive"))
    )
    (net (code "84") (name "VDD_DDR") (class "Default")
      (node (ref "C10") (pin "2") (pinfunction "2_2") (pintype "passive"))
      (node (ref "C11") (pin "2") (pinfunction "2_2") (pintype "passive"))
      (node (ref "C12") (pin "2") (pinfunction "2_2") (pintype "passive"))
      (node (ref "C15") (pin "2") (pinfunction "2_2") (pintype "passive"))
      (node (ref "C16") (pin "2") (pinfunction "2_2") (pintype "passive"))
      (node (ref "C17") (pin "2") (pinfunction "2_2") (pintype "passive"))
      (node (ref "C19") (pin "2") (pinfunction "2_2") (pintype "passive"))
      (node (ref "C20") (pin "2") (pinfunction "2_2") (pintype "passive"))
      (node (ref "C21") (pin "2") (pinfunction "2_2") (pintype "passive"))
      (node (ref "C22") (pin "1") (pinfunction "1_1") (pintype "passive"))
      (node (ref "C23") (pin "2") (pinfunction "2_2") (pintype "passive"))
      (node (ref "C24") (pin "2") (pinfunction "2_2") (pintype "passive"))
      (node (ref "C25") (pin "2") (pinfunction "2_2") (pintype "passive"))
      (node (ref "C27") (pin "2") (pinfunction "2_2") (pintype "passive"))
      (node (ref "C9") (pin "2") (pinfunction "2_2") (pintype "passive"))
      (node (ref "R28") (pin "2") (pinfunction "2_2") (pintype "passive"))
      (node (ref "R30") (pin "2") (pinfunction "2_2") (pintype "passive"))
      (node (ref "U2") (pin "A1") (pinfunction "VDDQ_A1") (pintype "power_in"))
      (node (ref "U2") (pin "A8") (pinfunction "VDDQ_A8") (pintype "power_in"))
      (node (ref "U2") (pin "B2") (pinfunction "VDD_B2") (pintype "power_in"))
      (node (ref "U2") (pin "C1") (pinfunction "VDDQ_C1") (pintype "power_in"))
      (node (ref "U2") (pin "C9") (pinfunction "VDDQ_C9") (pintype "power_in"))
      (node (ref "U2") (pin "D2") (pinfunction "VDDQ_D2") (pintype "power_in"))
      (node (ref "U2") (pin "D9") (pinfunction "VDD_D9") (pintype "power_in"))
      (node (ref "U2") (pin "E9") (pinfunction "VDDQ_E9") (pintype "power_in"))
      (node (ref "U2") (pin "F1") (pinfunction "VDDQ_F1") (pintype "power_in"))
      (node (ref "U2") (pin "G7") (pinfunction "VDD_G7") (pintype "power_in"))
      (node (ref "U2") (pin "H2") (pinfunction "VDDQ_H2") (pintype "power_in"))
      (node (ref "U2") (pin "H9") (pinfunction "VDDQ_H9") (pintype "power_in"))
      (node (ref "U2") (pin "K2") (pinfunction "VDD_K2") (pintype "power_in"))
      (node (ref "U2") (pin "K8") (pinfunction "VDD_K8") (pintype "power_in"))
      (node (ref "U2") (pin "N1") (pinfunction "VDD_N1") (pintype "power_in"))
      (node (ref "U2") (pin "N9") (pinfunction "VDD_N9") (pintype "power_in"))
      (node (ref "U2") (pin "R1") (pinfunction "VDD_R1") (pintype "power_in"))
      (node (ref "U2") (pin "R9") (pinfunction "VDD_R9") (pintype "power_in"))
    )
    (net (code "85") (name "unconnected-(U2-NC-PadJ1)") (class "Default")
      (node (ref "U2") (pin "J1") (pinfunction "NC_J1") (pintype "passive+no_connect"))
    )
    (net (code "86") (name "unconnected-(U2-NC-PadJ9)") (class "Default")
      (node (ref "U2") (pin "J9") (pinfunction "NC_J9") (pintype "passive+no_connect"))
    )
    (net (code "87") (name "unconnected-(U2-NC-PadL1)") (class "Default")
      (node (ref "U2") (pin "L1") (pinfunction "NC_L1") (pintype "passive+no_connect"))
    )
    (net (code "88") (name "unconnected-(U2-NC-PadL9)") (class "Default")
      (node (ref "U2") (pin "L9") (pinfunction "NC_L9") (pintype "passive+no_connect"))
    )
  )
)
